# GPSClock_Display.net
KiCad netlist of a schematic drawn in EAGLE
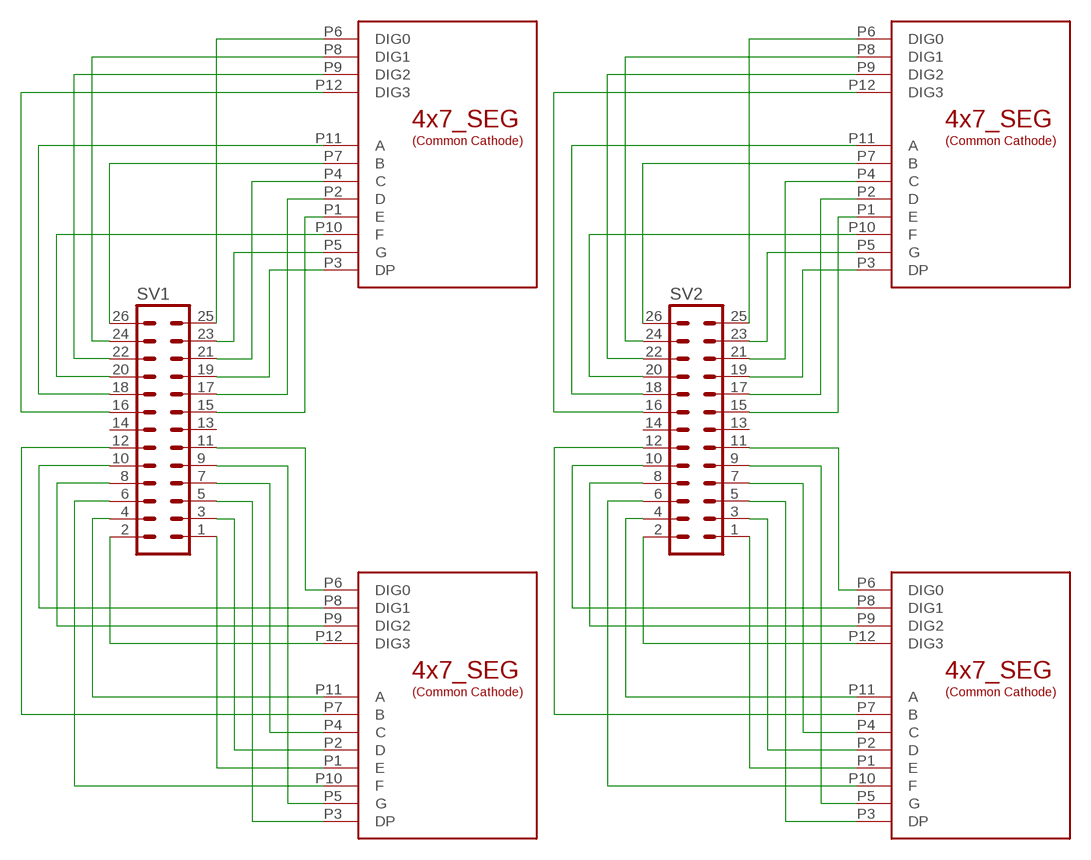
[diagram p0: schematic, sheet 1]

(export (version "E")
  (design (tool "Eeschema 10.0.6"))
  (components
    (comp (ref "SV1")
      (value "MA13-2")
      (footprint "eagle-import:MA13-2")
      (libsource (lib "eagle-import") (part "MA13-2"))
    )
    (comp (ref "SV2")
      (value "MA13-2")
      (footprint "eagle-import:MA13-2")
      (libsource (lib "eagle-import") (part "MA13-2"))
    )
    (comp (ref "U$1")
      (value "4X7_SEGTHROUGH_HOLE")
      (footprint "eagle-import:4X7_SEG")
      (libsource (lib "eagle-import") (part "4X7_SEGTHROUGH_HOLE"))
    )
    (comp (ref "U$2")
      (value "4X7_SEGTHROUGH_HOLE")
      (footprint "eagle-import:4X7_SEG")
      (libsource (lib "eagle-import") (part "4X7_SEGTHROUGH_HOLE"))
    )
    (comp (ref "U$3")
      (value "4X7_SEGTHROUGH_HOLE")
      (footprint "eagle-import:4X7_SEG")
      (libsource (lib "eagle-import") (part "4X7_SEGTHROUGH_HOLE"))
    )
    (comp (ref "U$4")
      (value "4X7_SEGTHROUGH_HOLE")
      (footprint "eagle-import:4X7_SEG")
      (libsource (lib "eagle-import") (part "4X7_SEGTHROUGH_HOLE"))
    )
  )
  (nets
    (net (code "1") (name "Net-(U$1-A)") (class "Default")
      (node (ref "SV1") (pin "18") (pinfunction "18_18") (pintype "passive"))
      (node (ref "U$1") (pin "P11") (pinfunction "A_P11") (pintype "bidirectional"))
    )
    (net (code "2") (name "Net-(U$1-B)") (class "Default")
      (node (ref "SV1") (pin "26") (pinfunction "26_26") (pintype "passive"))
      (node (ref "U$1") (pin "P7") (pinfunction "B_P7") (pintype "bidirectional"))
    )
    (net (code "3") (name "Net-(U$1-C)") (class "Default")
      (node (ref "SV1") (pin "21") (pinfunction "21_21") (pintype "passive"))
      (node (ref "U$1") (pin "P4") (pinfunction "C_P4") (pintype "bidirectional"))
    )
    (net (code "4") (name "Net-(U$1-D)") (class "Default")
      (node (ref "SV1") (pin "17") (pinfunction "17_17") (pintype "passive"))
      (node (ref "U$1") (pin "P2") (pinfunction "D_P2") (pintype "bidirectional"))
    )
    (net (code "5") (name "Net-(U$1-DIG0)") (class "Default")
      (node (ref "SV1") (pin "25") (pinfunction "25_25") (pintype "passive"))
      (node (ref "U$1") (pin "P6") (pinfunction "DIG0_P6") (pintype "bidirectional"))
    )
    (net (code "6") (name "Net-(U$1-DIG1)") (class "Default")
      (node (ref "SV1") (pin "24") (pinfunction "24_24") (pintype "passive"))
      (node (ref "U$1") (pin "P8") (pinfunction "DIG1_P8") (pintype "bidirectional"))
    )
    (net (code "7") (name "Net-(U$1-DIG2)") (class "Default")
      (node (ref "SV1") (pin "22") (pinfunction "22_22") (pintype "passive"))
      (node (ref "U$1") (pin "P9") (pinfunction "DIG2_P9") (pintype "bidirectional"))
    )
    (net (code "8") (name "Net-(U$1-DIG3)") (class "Default")
      (node (ref "SV1") (pin "16") (pinfunction "16_16") (pintype "passive"))
      (node (ref "U$1") (pin "P12") (pinfunction "DIG3_P12") (pintype "bidirectional"))
    )
    (net (code "9") (name "Net-(U$1-DP)") (class "Default")
      (node (ref "SV1") (pin "19") (pinfunction "19_19") (pintype "passive"))
      (node (ref "U$1") (pin "P3") (pinfunction "DP_P3") (pintype "bidirectional"))
    )
    (net (code "10") (name "Net-(U$1-E)") (class "Default")
      (node (ref "SV1") (pin "15") (pinfunction "15_15") (pintype "passive"))
      (node (ref "U$1") (pin "P1") (pinfunction "E_P1") (pintype "bidirectional"))
    )
    (net (code "11") (name "Net-(U$1-F)") (class "Default")
      (node (ref "SV1") (pin "20") (pinfunction "20_20") (pintype "passive"))
      (node (ref "U$1") (pin "P10") (pinfunction "F_P10") (pintype "bidirectional"))
    )
    (net (code "12") (name "Net-(U$1-G)") (class "Default")
      (node (ref "SV1") (pin "23") (pinfunction "23_23") (pintype "passive"))
      (node (ref "U$1") (pin "P5") (pinfunction "G_P5") (pintype "bidirectional"))
    )
    (net (code "13") (name "Net-(U$2-A)") (class "Default")
      (node (ref "SV1") (pin "4") (pinfunction "4_4") (pintype "passive"))
      (node (ref "U$2") (pin "P11") (pinfunction "A_P11") (pintype "bidirectional"))
    )
    (net (code "14") (name "Net-(U$2-B)") (class "Default")
      (node (ref "SV1") (pin "12") (pinfunction "12_12") (pintype "passive"))
      (node (ref "U$2") (pin "P7") (pinfunction "B_P7") (pintype "bidirectional"))
    )
    (net (code "15") (name "Net-(U$2-C)") (class "Default")
      (node (ref "SV1") (pin "7") (pinfunction "7_7") (pintype "passive"))
      (node (ref "U$2") (pin "P4") (pinfunction "C_P4") (pintype "bidirectional"))
    )
    (net (code "16") (name "Net-(U$2-D)") (class "Default")
      (node (ref "SV1") (pin "3") (pinfunction "3_3") (pintype "passive"))
      (node (ref "U$2") (pin "P2") (pinfunction "D_P2") (pintype "bidirectional"))
    )
    (net (code "17") (name "Net-(U$2-DIG0)") (class "Default")
      (node (ref "SV1") (pin "11") (pinfunction "11_11") (pintype "passive"))
      (node (ref "U$2") (pin "P6") (pinfunction "DIG0_P6") (pintype "bidirectional"))
    )
    (net (code "18") (name "Net-(U$2-DIG1)") (class "Default")
      (node (ref "SV1") (pin "10") (pinfunction "10_10") (pintype "passive"))
      (node (ref "U$2") (pin "P8") (pinfunction "DIG1_P8") (pintype "bidirectional"))
    )
    (net (code "19") (name "Net-(U$2-DIG2)") (class "Default")
      (node (ref "SV1") (pin "8") (pinfunction "8_8") (pintype "passive"))
      (node (ref "U$2") (pin "P9") (pinfunction "DIG2_P9") (pintype "bidirectional"))
    )
    (net (code "20") (name "Net-(U$2-DIG3)") (class "Default")
      (node (ref "SV1") (pin "2") (pinfunction "2_2") (pintype "passive"))
      (node (ref "U$2") (pin "P12") (pinfunction "DIG3_P12") (pintype "bidirectional"))
    )
    (net (code "21") (name "Net-(U$2-DP)") (class "Default")
      (node (ref "SV1") (pin "5") (pinfunction "5_5") (pintype "passive"))
      (node (ref "U$2") (pin "P3") (pinfunction "DP_P3") (pintype "bidirectional"))
    )
    (net (code "22") (name "Net-(U$2-E)") (class "Default")
      (node (ref "SV1") (pin "1") (pinfunction "1_1") (pintype "passive"))
      (node (ref "U$2") (pin "P1") (pinfunction "E_P1") (pintype "bidirectional"))
    )
    (net (code "23") (name "Net-(U$2-F)") (class "Default")
      (node (ref "SV1") (pin "6") (pinfunction "6_6") (pintype "passive"))
      (node (ref "U$2") (pin "P10") (pinfunction "F_P10") (pintype "bidirectional"))
    )
    (net (code "24") (name "Net-(U$2-G)") (class "Default")
      (node (ref "SV1") (pin "9") (pinfunction "9_9") (pintype "passive"))
      (node (ref "U$2") (pin "P5") (pinfunction "G_P5") (pintype "bidirectional"))
    )
    (net (code "25") (name "Net-(U$3-A)") (class "Default")
      (node (ref "SV2") (pin "18") (pinfunction "18_18") (pintype "passive"))
      (node (ref "U$3") (pin "P11") (pinfunction "A_P11") (pintype "bidirectional"))
    )
    (net (code "26") (name "Net-(U$3-B)") (class "Default")
      (node (ref "SV2") (pin "26") (pinfunction "26_26") (pintype "passive"))
      (node (ref "U$3") (pin "P7") (pinfunction "B_P7") (pintype "bidirectional"))
    )
    (net (code "27") (name "Net-(U$3-C)") (class "Default")
      (node (ref "SV2") (pin "21") (pinfunction "21_21") (pintype "passive"))
      (node (ref "U$3") (pin "P4") (pinfunction "C_P4") (pintype "bidirectional"))
    )
    (net (code "28") (name "Net-(U$3-D)") (class "Default")
      (node (ref "SV2") (pin "17") (pinfunction "17_17") (pintype "passive"))
      (node (ref "U$3") (pin "P2") (pinfunction "D_P2") (pintype "bidirectional"))
    )
    (net (code "29") (name "Net-(U$3-DIG0)") (class "Default")
      (node (ref "SV2") (pin "25") (pinfunction "25_25") (pintype "passive"))
      (node (ref "U$3") (pin "P6") (pinfunction "DIG0_P6") (pintype "bidirectional"))
    )
    (net (code "30") (name "Net-(U$3-DIG1)") (class "Default")
      (node (ref "SV2") (pin "24") (pinfunction "24_24") (pintype "passive"))
      (node (ref "U$3") (pin "P8") (pinfunction "DIG1_P8") (pintype "bidirectional"))
    )
    (net (code "31") (name "Net-(U$3-DIG2)") (class "Default")
      (node (ref "SV2") (pin "22") (pinfunction "22_22") (pintype "passive"))
      (node (ref "U$3") (pin "P9") (pinfunction "DIG2_P9") (pintype "bidirectional"))
    )
    (net (code "32") (name "Net-(U$3-DIG3)") (class "Default")
      (node (ref "SV2") (pin "16") (pinfunction "16_16") (pintype "passive"))
      (node (ref "U$3") (pin "P12") (pinfunction "DIG3_P12") (pintype "bidirectional"))
    )
    (net (code "33") (name "Net-(U$3-DP)") (class "Default")
      (node (ref "SV2") (pin "19") (pinfunction "19_19") (pintype "passive"))
      (node (ref "U$3") (pin "P3") (pinfunction "DP_P3") (pintype "bidirectional"))
    )
    (net (code "34") (name "Net-(U$3-E)") (class "Default")
      (node (ref "SV2") (pin "15") (pinfunction "15_15") (pintype "passive"))
      (node (ref "U$3") (pin "P1") (pinfunction "E_P1") (pintype "bidirectional"))
    )
    (net (code "35") (name "Net-(U$3-F)") (class "Default")
      (node (ref "SV2") (pin "20") (pinfunction "20_20") (pintype "passive"))
      (node (ref "U$3") (pin "P10") (pinfunction "F_P10") (pintype "bidirectional"))
    )
    (net (code "36") (name "Net-(U$3-G)") (class "Default")
      (node (ref "SV2") (pin "23") (pinfunction "23_23") (pintype "passive"))
      (node (ref "U$3") (pin "P5") (pinfunction "G_P5") (pintype "bidirectional"))
    )
    (net (code "37") (name "Net-(U$4-A)") (class "Default")
      (node (ref "SV2") (pin "4") (pinfunction "4_4") (pintype "passive"))
      (node (ref "U$4") (pin "P11") (pinfunction "A_P11") (pintype "bidirectional"))
    )
    (net (code "38") (name "Net-(U$4-B)") (class "Default")
      (node (ref "SV2") (pin "12") (pinfunction "12_12") (pintype "passive"))
      (node (ref "U$4") (pin "P7") (pinfunction "B_P7") (pintype "bidirectional"))
    )
    (net (code "39") (name "Net-(U$4-C)") (class "Default")
      (node (ref "SV2") (pin "7") (pinfunction "7_7") (pintype "passive"))
      (node (ref "U$4") (pin "P4") (pinfunction "C_P4") (pintype "bidirectional"))
    )
    (net (code "40") (name "Net-(U$4-D)") (class "Default")
      (node (ref "SV2") (pin "3") (pinfunction "3_3") (pintype "passive"))
      (node (ref "U$4") (pin "P2") (pinfunction "D_P2") (pintype "bidirectional"))
    )
    (net (code "41") (name "Net-(U$4-DIG0)") (class "Default")
      (node (ref "SV2") (pin "11") (pinfunction "11_11") (pintype "passive"))
      (node (ref "U$4") (pin "P6") (pinfunction "DIG0_P6") (pintype "bidirectional"))
    )
    (net (code "42") (name "Net-(U$4-DIG1)") (class "Default")
      (node (ref "SV2") (pin "10") (pinfunction "10_10") (pintype "passive"))
      (node (ref "U$4") (pin "P8") (pinfunction "DIG1_P8") (pintype "bidirectional"))
    )
    (net (code "43") (name "Net-(U$4-DIG2)") (class "Default")
      (node (ref "SV2") (pin "8") (pinfunction "8_8") (pintype "passive"))
      (node (ref "U$4") (pin "P9") (pinfunction "DIG2_P9") (pintype "bidirectional"))
    )
    (net (code "44") (name "Net-(U$4-DIG3)") (class "Default")
      (node (ref "SV2") (pin "2") (pinfunction "2_2") (pintype "passive"))
      (node (ref "U$4") (pin "P12") (pinfunction "DIG3_P12") (pintype "bidirectional"))
    )
    (net (code "45") (name "Net-(U$4-DP)") (class "Default")
      (node (ref "SV2") (pin "5") (pinfunction "5_5") (pintype "passive"))
      (node (ref "U$4") (pin "P3") (pinfunction "DP_P3") (pintype "bidirectional"))
    )
    (net (code "46") (name "Net-(U$4-E)") (class "Default")
      (node (ref "SV2") (pin "1") (pinfunction "1_1") (pintype "passive"))
      (node (ref "U$4") (pin "P1") (pinfunction "E_P1") (pintype "bidirectional"))
    )
    (net (code "47") (name "Net-(U$4-F)") (class "Default")
      (node (ref "SV2") (pin "6") (pinfunction "6_6") (pintype "passive"))
      (node (ref "U$4") (pin "P10") (pinfunction "F_P10") (pintype "bidirectional"))
    )
    (net (code "48") (name "Net-(U$4-G)") (class "Default")
      (node (ref "SV2") (pin "9") (pinfunction "9_9") (pintype "passive"))
      (node (ref "U$4") (pin "P5") (pinfunction "G_P5") (pintype "bidirectional"))
    )
    (net (code "49") (name "unconnected-(SV1-Pad13)") (class "Default")
      (node (ref "SV1") (pin "13") (pinfunction "13_13") (pintype "passive"))
    )
    (net (code "50") (name "unconnected-(SV1-Pad14)") (class "Default")
      (node (ref "SV1") (pin "14") (pinfunction "14_14") (pintype "passive"))
    )
    (net (code "51") (name "unconnected-(SV2-Pad13)") (class "Default")
      (node (ref "SV2") (pin "13") (pinfunction "13_13") (pintype "passive"))
    )
    (net (code "52") (name "unconnected-(SV2-Pad14)") (class "Default")
      (node (ref "SV2") (pin "14") (pinfunction "14_14") (pintype "passive"))
    )
  )
)
